# SparkFun_Interactive_Badge.net
KiCad netlist of a schematic drawn in EAGLE
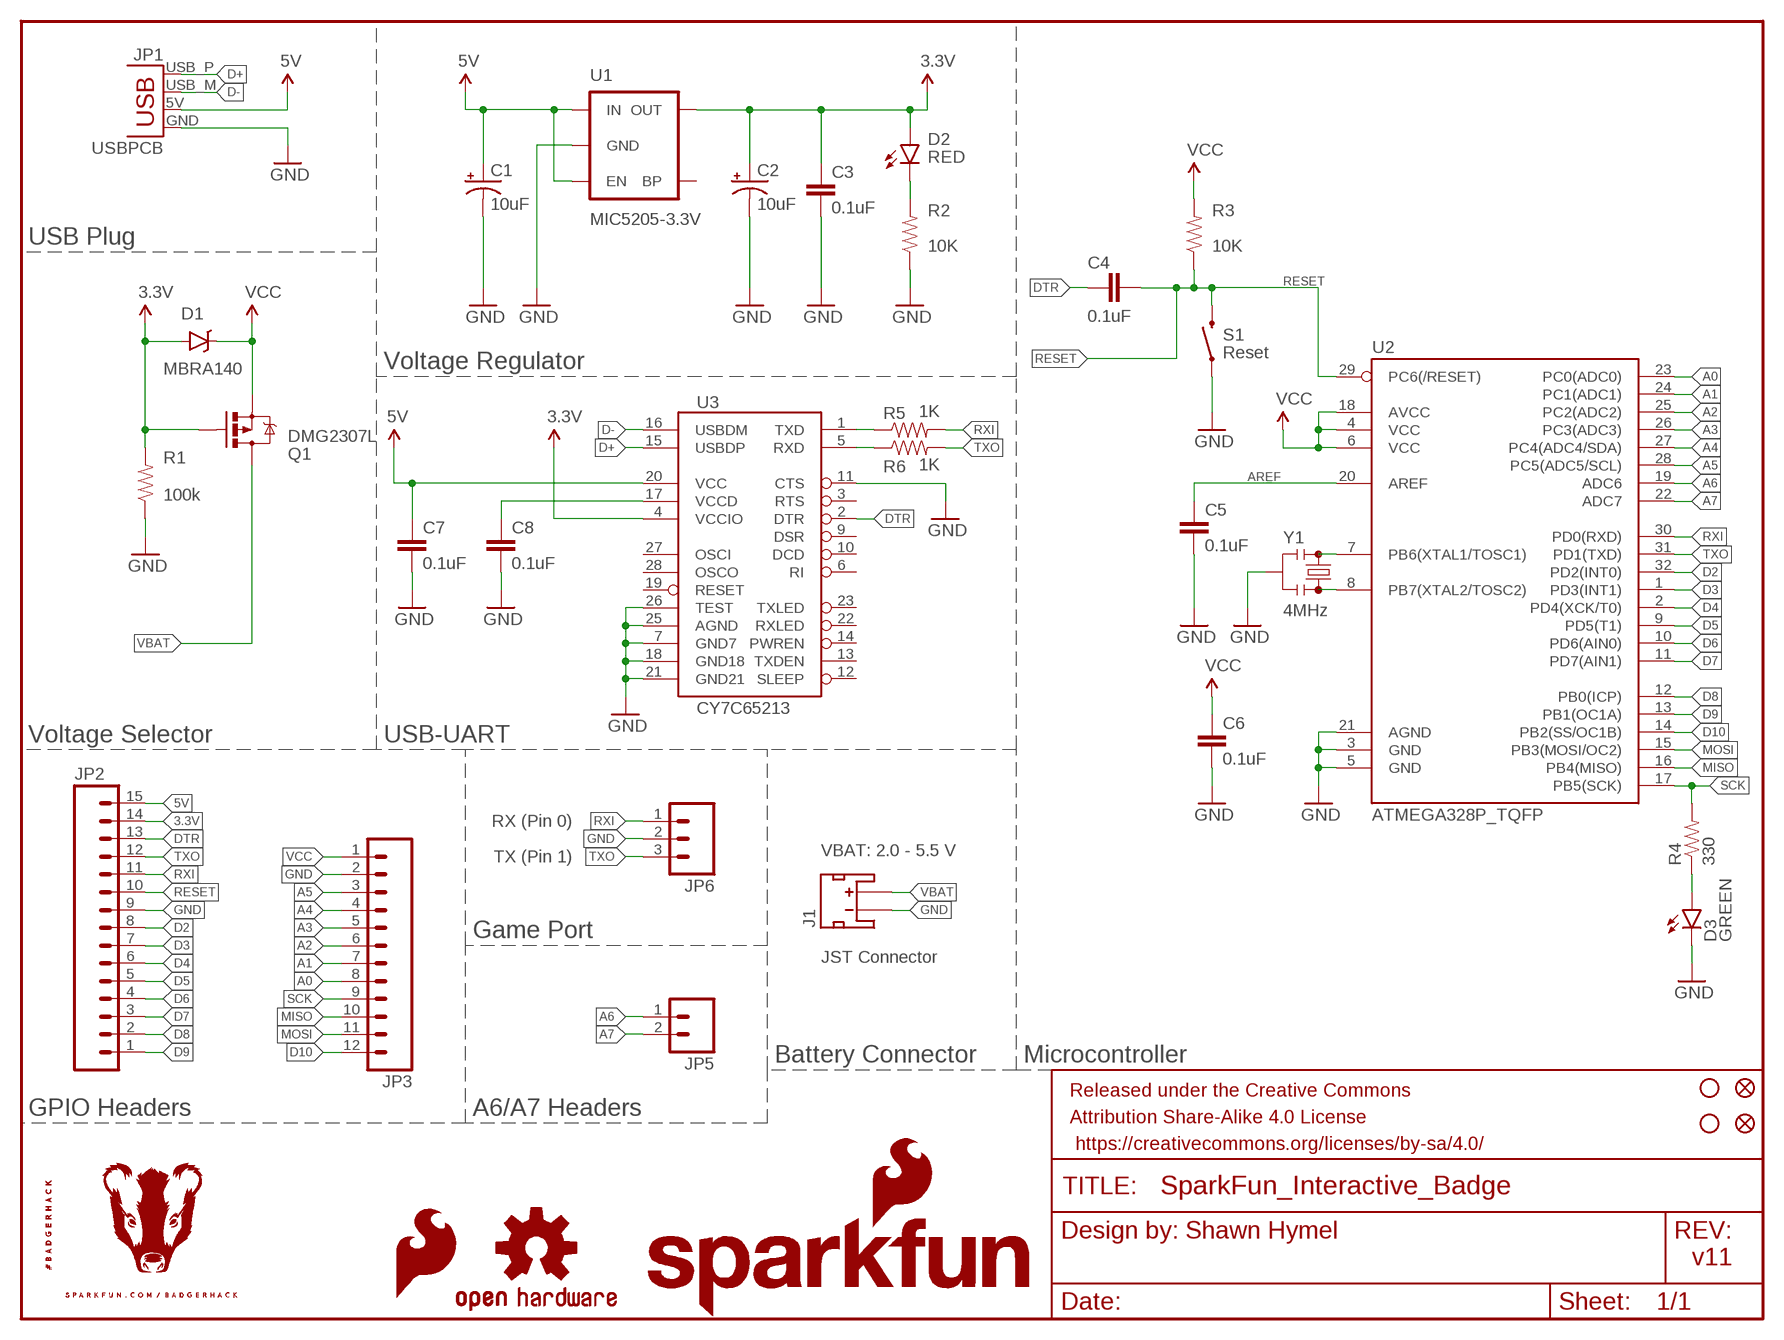
[diagram p0: schematic, sheet 1]

(export (version "E")
  (design (tool "Eeschema 10.0.6"))
  (components
    (comp (ref "C1")
      (value "10uF")
      (footprint "eagle-import:EIA3216")
      (libsource (lib "eagle-import") (part "10UF-16V-10%(TANT)"))
    )
    (comp (ref "C2")
      (value "10uF")
      (footprint "eagle-import:EIA3216")
      (libsource (lib "eagle-import") (part "10UF-16V-10%(TANT)"))
    )
    (comp (ref "C3")
      (value "0.1uF")
      (footprint "eagle-import:0603-CAP")
      (libsource (lib "eagle-import") (part "0.1UF-25V(+80/-20%)(0603)"))
    )
    (comp (ref "C4")
      (value "0.1uF")
      (footprint "eagle-import:0603-CAP")
      (libsource (lib "eagle-import") (part "0.1UF-25V(+80/-20%)(0603)"))
    )
    (comp (ref "C5")
      (value "0.1uF")
      (footprint "eagle-import:0603-CAP")
      (libsource (lib "eagle-import") (part "0.1UF-25V(+80/-20%)(0603)"))
    )
    (comp (ref "C6")
      (value "0.1uF")
      (footprint "eagle-import:0603-CAP")
      (libsource (lib "eagle-import") (part "0.1UF-25V(+80/-20%)(0603)"))
    )
    (comp (ref "C7")
      (value "0.1uF")
      (footprint "eagle-import:0603-CAP")
      (libsource (lib "eagle-import") (part "0.1UF-25V(+80/-20%)(0603)"))
    )
    (comp (ref "C8")
      (value "0.1uF")
      (footprint "eagle-import:0603-CAP")
      (libsource (lib "eagle-import") (part "0.1UF-25V(+80/-20%)(0603)"))
    )
    (comp (ref "D1")
      (value "MBRA140")
      (footprint "eagle-import:SMA-DIODE")
      (libsource (lib "eagle-import") (part "DIODE-SCHOTTKY-MBRA140"))
    )
    (comp (ref "D2")
      (value "RED")
      (footprint "eagle-import:LED-0603")
      (libsource (lib "eagle-import") (part "LED-RED0603"))
    )
    (comp (ref "D3")
      (value "GREEN")
      (footprint "eagle-import:LED-0603")
      (libsource (lib "eagle-import") (part "LED-GREEN0603"))
    )
    (comp (ref "FID1")
      (value "FIDUCIAL1X2")
      (footprint "eagle-import:FIDUCIAL-1X2")
      (libsource (lib "eagle-import") (part "FIDUCIAL1X2"))
    )
    (comp (ref "FID2")
      (value "FIDUCIAL1X2")
      (footprint "eagle-import:FIDUCIAL-1X2")
      (libsource (lib "eagle-import") (part "FIDUCIAL1X2"))
    )
    (comp (ref "FRAME1")
      (value "FRAME-LETTER")
      (footprint "eagle-import:CREATIVE_COMMONS")
      (fields
        (field (name "DESIGNER") "NAME")
        (field (name "VERSION") "v01")
        (field (name "DESIGNER_1") "Shawn Hymel")
        (field (name "VERSION_1") "v11")
      )
      (libsource (lib "eagle-import") (part "FRAME-LETTER"))
    )
    (comp (ref "J1")
      (value "JST_2MM_MALE")
      (footprint "eagle-import:JST-2-SMD")
      (libsource (lib "eagle-import") (part "JST_2MM_MALE"))
    )
    (comp (ref "JP1")
      (value "USBPCB")
      (footprint "eagle-import:USB-A-PCB")
      (libsource (lib "eagle-import") (part "USBPCB"))
    )
    (comp (ref "JP2")
      (value "M15LOCK_NO_SILK")
      (footprint "eagle-import:1X15_LOCK_NO_SILK")
      (libsource (lib "eagle-import") (part "M15LOCK_NO_SILK"))
    )
    (comp (ref "JP3")
      (value "M12LOCK_NO_SILK")
      (footprint "eagle-import:1X12_LOCK_NO_SILK")
      (libsource (lib "eagle-import") (part "M12LOCK_NO_SILK"))
    )
    (comp (ref "JP5")
      (value "M021X02_NO_SILK")
      (footprint "eagle-import:1X02_NO_SILK")
      (libsource (lib "eagle-import") (part "M021X02_NO_SILK"))
    )
    (comp (ref "JP6")
      (value "M03LOCK Female")
      (footprint "eagle-import:1X03_LOCK_NO_SILK")
      (libsource (lib "eagle-import") (part "M03LOCK_NO_SILK"))
    )
    (comp (ref "LOGO1")
      (value "SFE_LOGO_FLAME.1_INCH")
      (footprint "eagle-import:SFE_LOGO_FLAME_.1")
      (libsource (lib "eagle-import") (part "SFE_LOGO_FLAME.1_INCH"))
    )
    (comp (ref "LOGO2")
      (value "OSHW-LOGOS")
      (footprint "eagle-import:OSHW-LOGO-S")
      (libsource (lib "eagle-import") (part "OSHW-LOGOS"))
    )
    (comp (ref "Q1")
      (value "DMG2307L")
      (footprint "eagle-import:SOT23-3")
      (libsource (lib "eagle-import") (part "MOSFET-PCHANNELDMG2307L"))
    )
    (comp (ref "R1")
      (value "100k")
      (footprint "eagle-import:0603-RES")
      (libsource (lib "eagle-import") (part "100KOHM-1/10W-1%(0603)"))
    )
    (comp (ref "R2")
      (value "10K")
      (footprint "eagle-import:0603-RES")
      (libsource (lib "eagle-import") (part "10KOHM-1/10W-1%(0603)0603"))
    )
    (comp (ref "R3")
      (value "10K")
      (footprint "eagle-import:0603-RES")
      (libsource (lib "eagle-import") (part "10KOHM-1/10W-1%(0603)0603"))
    )
    (comp (ref "R4")
      (value "330")
      (footprint "eagle-import:0603-RES")
      (libsource (lib "eagle-import") (part "330OHM1/10W1%(0603)"))
    )
    (comp (ref "R5")
      (value "1K")
      (footprint "eagle-import:0603-RES")
      (libsource (lib "eagle-import") (part "1KOHM-1/10W-1%(0603)"))
    )
    (comp (ref "R6")
      (value "1K")
      (footprint "eagle-import:0603-RES")
      (libsource (lib "eagle-import") (part "1KOHM-1/10W-1%(0603)"))
    )
    (comp (ref "S1")
      (value "SWITCH-MOMENTARY-2SMD-REDUNDANT")
      (footprint "eagle-import:TACTILE-SWITCH-SMD")
      (fields (field (name "FUNC") "Reset"))
      (libsource (lib "eagle-import") (part "SWITCH-MOMENTARY-2SMD-REDUNDANT"))
    )
    (comp (ref "STANDOFF1")
      (value "STAND-OFF")
      (footprint "eagle-import:STAND-OFF")
      (libsource (lib "eagle-import") (part "STAND-OFF"))
    )
    (comp (ref "STANDOFF2")
      (value "STAND-OFF")
      (footprint "eagle-import:STAND-OFF")
      (libsource (lib "eagle-import") (part "STAND-OFF"))
    )
    (comp (ref "U$1")
      (value "SFE_LOGO_NAME_FLAME.1_INCH")
      (footprint "eagle-import:SFE_LOGO_NAME_FLAME_.1")
      (libsource (lib "eagle-import") (part "SFE_LOGO_NAME_FLAME.1_INCH"))
    )
    (comp (ref "U$2")
      (value "BADGERHACK_LOGODUMMY")
      (footprint "eagle-import:DUMMY")
      (libsource (lib "eagle-import") (part "BADGERHACK_LOGODUMMY"))
    )
    (comp (ref "U1")
      (value "MIC5205-3.3V")
      (footprint "eagle-import:SOT23-5")
      (libsource (lib "eagle-import") (part "MIC52053.3V"))
    )
    (comp (ref "U2")
      (value "ATMEGA328P_TQFP")
      (footprint "eagle-import:TQFP32-08")
      (libsource (lib "eagle-import") (part "ATMEGA328P_TQFP"))
    )
    (comp (ref "U3")
      (value "CY7C65213")
      (footprint "eagle-import:SSOP28DB")
      (libsource (lib "eagle-import") (part "CY7C65213"))
    )
    (comp (ref "Y1")
      (value "4MHz")
      (footprint "eagle-import:RESONATOR-SMD_MED")
      (libsource (lib "eagle-import") (part "RESONATOR4MHZ"))
    )
  )
  (nets
    (net (code "1") (name "/AREF") (class "Default")
      (node (ref "C5") (pin "1") (pinfunction "1_1") (pintype "passive"))
      (node (ref "U2") (pin "20") (pinfunction "AREF_20") (pintype "bidirectional"))
    )
    (net (code "2") (name "3.3V") (class "Default")
      (node (ref "C2") (pin "A") (pinfunction "+_A") (pintype "passive"))
      (node (ref "C3") (pin "1") (pinfunction "1_1") (pintype "passive"))
      (node (ref "D1") (pin "A") (pinfunction "A_A") (pintype "passive"))
      (node (ref "D2") (pin "A") (pinfunction "A_A") (pintype "passive"))
      (node (ref "JP2") (pin "14") (pinfunction "14_14") (pintype "passive"))
      (node (ref "Q1") (pin "1") (pinfunction "G_1") (pintype "passive"))
      (node (ref "R1") (pin "2") (pinfunction "2_2") (pintype "passive"))
      (node (ref "U1") (pin "5") (pinfunction "OUT_5") (pintype "passive"))
      (node (ref "U3") (pin "4") (pinfunction "VCCIO_4") (pintype "power_in"))
    )
    (net (code "3") (name "5V") (class "Default")
      (node (ref "C1") (pin "A") (pinfunction "+_A") (pintype "passive"))
      (node (ref "C7") (pin "1") (pinfunction "1_1") (pintype "passive"))
      (node (ref "JP1") (pin "5V") (pinfunction "VBUS_5V") (pintype "bidirectional"))
      (node (ref "JP2") (pin "15") (pinfunction "15_15") (pintype "passive"))
      (node (ref "U1") (pin "1") (pinfunction "IN_1") (pintype "input"))
      (node (ref "U1") (pin "3") (pinfunction "EN_3") (pintype "input"))
      (node (ref "U3") (pin "20") (pinfunction "VCC_20") (pintype "power_in"))
    )
    (net (code "4") (name "A0") (class "Default")
      (node (ref "JP3") (pin "8") (pinfunction "8_8") (pintype "passive"))
      (node (ref "U2") (pin "23") (pinfunction "PC0(ADC0)_23") (pintype "bidirectional"))
    )
    (net (code "5") (name "A1") (class "Default")
      (node (ref "JP3") (pin "7") (pinfunction "7_7") (pintype "passive"))
      (node (ref "U2") (pin "24") (pinfunction "PC1(ADC1)_24") (pintype "bidirectional"))
    )
    (net (code "6") (name "A2") (class "Default")
      (node (ref "JP3") (pin "6") (pinfunction "6_6") (pintype "passive"))
      (node (ref "U2") (pin "25") (pinfunction "PC2(ADC2)_25") (pintype "bidirectional"))
    )
    (net (code "7") (name "A3") (class "Default")
      (node (ref "JP3") (pin "5") (pinfunction "5_5") (pintype "passive"))
      (node (ref "U2") (pin "26") (pinfunction "PC3(ADC3)_26") (pintype "bidirectional"))
    )
    (net (code "8") (name "A4") (class "Default")
      (node (ref "JP3") (pin "4") (pinfunction "4_4") (pintype "passive"))
      (node (ref "U2") (pin "27") (pinfunction "PC4(ADC4/SDA)_27") (pintype "bidirectional"))
    )
    (net (code "9") (name "A5") (class "Default")
      (node (ref "JP3") (pin "3") (pinfunction "3_3") (pintype "passive"))
      (node (ref "U2") (pin "28") (pinfunction "PC5(ADC5/SCL)_28") (pintype "bidirectional"))
    )
    (net (code "10") (name "A6") (class "Default")
      (node (ref "JP5") (pin "1") (pinfunction "1_1") (pintype "passive"))
      (node (ref "U2") (pin "19") (pinfunction "ADC6_19") (pintype "bidirectional"))
    )
    (net (code "11") (name "A7") (class "Default")
      (node (ref "JP5") (pin "2") (pinfunction "2_2") (pintype "passive"))
      (node (ref "U2") (pin "22") (pinfunction "ADC7_22") (pintype "bidirectional"))
    )
    (net (code "12") (name "D+") (class "Default")
      (node (ref "JP1") (pin "USB_P") (pinfunction "D+_USB_P") (pintype "bidirectional"))
      (node (ref "U3") (pin "15") (pinfunction "USBDP_15") (pintype "bidirectional"))
    )
    (net (code "13") (name "D-") (class "Default")
      (node (ref "JP1") (pin "USB_M") (pinfunction "D-_USB_M") (pintype "bidirectional"))
      (node (ref "U3") (pin "16") (pinfunction "USBDM_16") (pintype "bidirectional"))
    )
    (net (code "14") (name "D2") (class "Default")
      (node (ref "JP2") (pin "8") (pinfunction "8_8") (pintype "passive"))
      (node (ref "U2") (pin "32") (pinfunction "PD2(INT0)_32") (pintype "bidirectional"))
    )
    (net (code "15") (name "D3") (class "Default")
      (node (ref "JP2") (pin "7") (pinfunction "7_7") (pintype "passive"))
      (node (ref "U2") (pin "1") (pinfunction "PD3(INT1)_1") (pintype "bidirectional"))
    )
    (net (code "16") (name "D4") (class "Default")
      (node (ref "JP2") (pin "6") (pinfunction "6_6") (pintype "passive"))
      (node (ref "U2") (pin "2") (pinfunction "PD4(XCK/T0)_2") (pintype "bidirectional"))
    )
    (net (code "17") (name "D5") (class "Default")
      (node (ref "JP2") (pin "5") (pinfunction "5_5") (pintype "passive"))
      (node (ref "U2") (pin "9") (pinfunction "PD5(T1)_9") (pintype "bidirectional"))
    )
    (net (code "18") (name "D6") (class "Default")
      (node (ref "JP2") (pin "4") (pinfunction "4_4") (pintype "passive"))
      (node (ref "U2") (pin "10") (pinfunction "PD6(AIN0)_10") (pintype "bidirectional"))
    )
    (net (code "19") (name "D7") (class "Default")
      (node (ref "JP2") (pin "3") (pinfunction "3_3") (pintype "passive"))
      (node (ref "U2") (pin "11") (pinfunction "PD7(AIN1)_11") (pintype "bidirectional"))
    )
    (net (code "20") (name "D8") (class "Default")
      (node (ref "JP2") (pin "2") (pinfunction "2_2") (pintype "passive"))
      (node (ref "U2") (pin "12") (pinfunction "PB0(ICP)_12") (pintype "bidirectional"))
    )
    (net (code "21") (name "D9") (class "Default")
      (node (ref "JP2") (pin "1") (pinfunction "1_1") (pintype "passive"))
      (node (ref "U2") (pin "13") (pinfunction "PB1(OC1A)_13") (pintype "bidirectional"))
    )
    (net (code "22") (name "D10") (class "Default")
      (node (ref "JP3") (pin "12") (pinfunction "12_12") (pintype "passive"))
      (node (ref "U2") (pin "14") (pinfunction "PB2(SS/OC1B)_14") (pintype "bidirectional"))
    )
    (net (code "23") (name "DTR") (class "Default")
      (node (ref "C4") (pin "1") (pinfunction "1_1") (pintype "passive"))
      (node (ref "JP2") (pin "13") (pinfunction "13_13") (pintype "passive"))
      (node (ref "U3") (pin "2") (pinfunction "DTR_2") (pintype "output"))
    )
    (net (code "24") (name "GND") (class "Default")
      (node (ref "C1") (pin "C") (pinfunction "-_C") (pintype "passive"))
      (node (ref "C2") (pin "C") (pinfunction "-_C") (pintype "passive"))
      (node (ref "C3") (pin "2") (pinfunction "2_2") (pintype "passive"))
      (node (ref "C5") (pin "2") (pinfunction "2_2") (pintype "passive"))
      (node (ref "C6") (pin "2") (pinfunction "2_2") (pintype "passive"))
      (node (ref "C7") (pin "2") (pinfunction "2_2") (pintype "passive"))
      (node (ref "C8") (pin "2") (pinfunction "2_2") (pintype "passive"))
      (node (ref "D3") (pin "C") (pinfunction "C_C") (pintype "passive"))
      (node (ref "J1") (pin "1") (pinfunction "-_1") (pintype "bidirectional"))
      (node (ref "JP1") (pin "GND") (pinfunction "GND_GND") (pintype "bidirectional"))
      (node (ref "JP2") (pin "9") (pinfunction "9_9") (pintype "passive"))
      (node (ref "JP3") (pin "2") (pinfunction "2_2") (pintype "passive"))
      (node (ref "JP6") (pin "2") (pinfunction "2_2") (pintype "passive"))
      (node (ref "R1") (pin "1") (pinfunction "1_1") (pintype "passive"))
      (node (ref "R2") (pin "1") (pinfunction "1_1") (pintype "passive"))
      (node (ref "S1") (pin "1") (pinfunction "1_1") (pintype "passive"))
      (node (ref "S1") (pin "2") (pinfunction "1_2") (pintype "passive"))
      (node (ref "U1") (pin "2") (pinfunction "GND_2") (pintype "input"))
      (node (ref "U2") (pin "21") (pinfunction "AGND_21") (pintype "bidirectional"))
      (node (ref "U2") (pin "3") (pinfunction "GND_3") (pintype "bidirectional"))
      (node (ref "U2") (pin "5") (pinfunction "GND_5") (pintype "bidirectional"))
      (node (ref "U3") (pin "11") (pinfunction "CTS_11") (pintype "input"))
      (node (ref "U3") (pin "18") (pinfunction "GND18_18") (pintype "power_in"))
      (node (ref "U3") (pin "21") (pinfunction "GND21_21") (pintype "power_in"))
      (node (ref "U3") (pin "25") (pinfunction "AGND_25") (pintype "power_in"))
      (node (ref "U3") (pin "26") (pinfunction "TEST_26") (pintype "input"))
      (node (ref "U3") (pin "7") (pinfunction "GND7_7") (pintype "power_in"))
      (node (ref "Y1") (pin "2") (pinfunction "2_2") (pintype "passive"))
    )
    (net (code "25") (name "MISO") (class "Default")
      (node (ref "JP3") (pin "10") (pinfunction "10_10") (pintype "passive"))
      (node (ref "U2") (pin "16") (pinfunction "PB4(MISO)_16") (pintype "bidirectional"))
    )
    (net (code "26") (name "MOSI") (class "Default")
      (node (ref "JP3") (pin "11") (pinfunction "11_11") (pintype "passive"))
      (node (ref "U2") (pin "15") (pinfunction "PB3(MOSI/OC2)_15") (pintype "bidirectional"))
    )
    (net (code "27") (name "Net-(D2-PadC)") (class "Default")
      (node (ref "D2") (pin "C") (pinfunction "C_C") (pintype "passive"))
      (node (ref "R2") (pin "2") (pinfunction "2_2") (pintype "passive"))
    )
    (net (code "28") (name "Net-(D3-PadA)") (class "Default")
      (node (ref "D3") (pin "A") (pinfunction "A_A") (pintype "passive"))
      (node (ref "R4") (pin "1") (pinfunction "1_1") (pintype "passive"))
    )
    (net (code "29") (name "Net-(U2-PB6(XTAL1{slash}TOSC1))") (class "Default")
      (node (ref "U2") (pin "7") (pinfunction "PB6(XTAL1/TOSC1)_7") (pintype "bidirectional"))
      (node (ref "Y1") (pin "1") (pinfunction "1_1") (pintype "passive"))
    )
    (net (code "30") (name "Net-(U2-PB7(XTAL2{slash}TOSC2))") (class "Default")
      (node (ref "U2") (pin "8") (pinfunction "PB7(XTAL2/TOSC2)_8") (pintype "bidirectional"))
      (node (ref "Y1") (pin "3") (pinfunction "3_3") (pintype "passive"))
    )
    (net (code "31") (name "Net-(U3-RXD)") (class "Default")
      (node (ref "R6") (pin "1") (pinfunction "1_1") (pintype "passive"))
      (node (ref "U3") (pin "5") (pinfunction "RXD_5") (pintype "input"))
    )
    (net (code "32") (name "Net-(U3-TXD)") (class "Default")
      (node (ref "R5") (pin "1") (pinfunction "1_1") (pintype "passive"))
      (node (ref "U3") (pin "1") (pinfunction "TXD_1") (pintype "output"))
    )
    (net (code "33") (name "Net-(U3-VCCD)") (class "Default")
      (node (ref "C8") (pin "1") (pinfunction "1_1") (pintype "passive"))
      (node (ref "U3") (pin "17") (pinfunction "VCCD_17") (pintype "output"))
    )
    (net (code "34") (name "RESET") (class "Default")
      (node (ref "C4") (pin "2") (pinfunction "2_2") (pintype "passive"))
      (node (ref "JP2") (pin "10") (pinfunction "10_10") (pintype "passive"))
      (node (ref "R3") (pin "1") (pinfunction "1_1") (pintype "passive"))
      (node (ref "S1") (pin "3") (pinfunction "2_3") (pintype "passive"))
      (node (ref "S1") (pin "4") (pinfunction "2_4") (pintype "passive"))
      (node (ref "U2") (pin "29") (pinfunction "PC6(/RESET)_29") (pintype "bidirectional"))
    )
    (net (code "35") (name "RXI") (class "Default")
      (node (ref "JP2") (pin "11") (pinfunction "11_11") (pintype "passive"))
      (node (ref "JP6") (pin "1") (pinfunction "1_1") (pintype "passive"))
      (node (ref "R5") (pin "2") (pinfunction "2_2") (pintype "passive"))
      (node (ref "U2") (pin "30") (pinfunction "PD0(RXD)_30") (pintype "bidirectional"))
    )
    (net (code "36") (name "SCK") (class "Default")
      (node (ref "JP3") (pin "9") (pinfunction "9_9") (pintype "passive"))
      (node (ref "R4") (pin "2") (pinfunction "2_2") (pintype "passive"))
      (node (ref "U2") (pin "17") (pinfunction "PB5(SCK)_17") (pintype "bidirectional"))
    )
    (net (code "37") (name "TXO") (class "Default")
      (node (ref "JP2") (pin "12") (pinfunction "12_12") (pintype "passive"))
      (node (ref "JP6") (pin "3") (pinfunction "3_3") (pintype "passive"))
      (node (ref "R6") (pin "2") (pinfunction "2_2") (pintype "passive"))
      (node (ref "U2") (pin "31") (pinfunction "PD1(TXD)_31") (pintype "bidirectional"))
    )
    (net (code "38") (name "VBAT") (class "Default")
      (node (ref "J1") (pin "2") (pinfunction "+_2") (pintype "bidirectional"))
      (node (ref "Q1") (pin "3") (pinfunction "D_3") (pintype "passive"))
    )
    (net (code "39") (name "VCC") (class "Default")
      (node (ref "C6") (pin "1") (pinfunction "1_1") (pintype "passive"))
      (node (ref "D1") (pin "C") (pinfunction "C_C") (pintype "passive"))
      (node (ref "JP3") (pin "1") (pinfunction "1_1") (pintype "passive"))
      (node (ref "Q1") (pin "2") (pinfunction "S_2") (pintype "passive"))
      (node (ref "R3") (pin "2") (pinfunction "2_2") (pintype "passive"))
      (node (ref "U2") (pin "18") (pinfunction "AVCC_18") (pintype "bidirectional"))
      (node (ref "U2") (pin "4") (pinfunction "VCC_4") (pintype "bidirectional"))
      (node (ref "U2") (pin "6") (pinfunction "VCC_6") (pintype "bidirectional"))
    )
    (net (code "40") (name "unconnected-(J1-PAD1-PadNC1)") (class "Default")
      (node (ref "J1") (pin "NC1") (pinfunction "PAD1_NC1") (pintype "bidirectional"))
    )
    (net (code "41") (name "unconnected-(J1-PAD2-PadNC2)") (class "Default")
      (node (ref "J1") (pin "NC2") (pinfunction "PAD2_NC2") (pintype "bidirectional"))
    )
    (net (code "42") (name "unconnected-(U1-BP-Pad4)") (class "Default")
      (node (ref "U1") (pin "4") (pinfunction "BP_4") (pintype "input"))
    )
    (net (code "43") (name "unconnected-(U3-DCD-Pad10)") (class "Default")
      (node (ref "U3") (pin "10") (pinfunction "DCD_10") (pintype "input"))
    )
    (net (code "44") (name "unconnected-(U3-DSR-Pad9)") (class "Default")
      (node (ref "U3") (pin "9") (pinfunction "DSR_9") (pintype "input"))
    )
    (net (code "45") (name "unconnected-(U3-OSCI-Pad27)") (class "Default")
      (node (ref "U3") (pin "27") (pinfunction "OSCI_27") (pintype "input"))
    )
    (net (code "46") (name "unconnected-(U3-OSCO-Pad28)") (class "Default")
      (node (ref "U3") (pin "28") (pinfunction "OSCO_28") (pintype "output"))
    )
    (net (code "47") (name "unconnected-(U3-PWREN-Pad14)") (class "Default")
      (node (ref "U3") (pin "14") (pinfunction "PWREN_14") (pintype "input"))
    )
    (net (code "48") (name "unconnected-(U3-RESET-Pad19)") (class "Default")
      (node (ref "U3") (pin "19") (pinfunction "RESET_19") (pintype "input"))
    )
    (net (code "49") (name "unconnected-(U3-RI-Pad6)") (class "Default")
      (node (ref "U3") (pin "6") (pinfunction "RI_6") (pintype "input"))
    )
    (net (code "50") (name "unconnected-(U3-RTS-Pad3)") (class "Default")
      (node (ref "U3") (pin "3") (pinfunction "RTS_3") (pintype "output"))
    )
    (net (code "51") (name "unconnected-(U3-RXLED-Pad22)") (class "Default")
      (node (ref "U3") (pin "22") (pinfunction "RXLED_22") (pintype "input"))
    )
    (net (code "52") (name "unconnected-(U3-SLEEP-Pad12)") (class "Default")
      (node (ref "U3") (pin "12") (pinfunction "SLEEP_12") (pintype "input"))
    )
    (net (code "53") (name "unconnected-(U3-TXDEN-Pad13)") (class "Default")
      (node (ref "U3") (pin "13") (pinfunction "TXDEN_13") (pintype "input"))
    )
    (net (code "54") (name "unconnected-(U3-TXLED-Pad23)") (class "Default")
      (node (ref "U3") (pin "23") (pinfunction "TXLED_23") (pintype "input"))
    )
  )
)
